# Uno.net
KiCad netlist of a schematic drawn in EAGLE
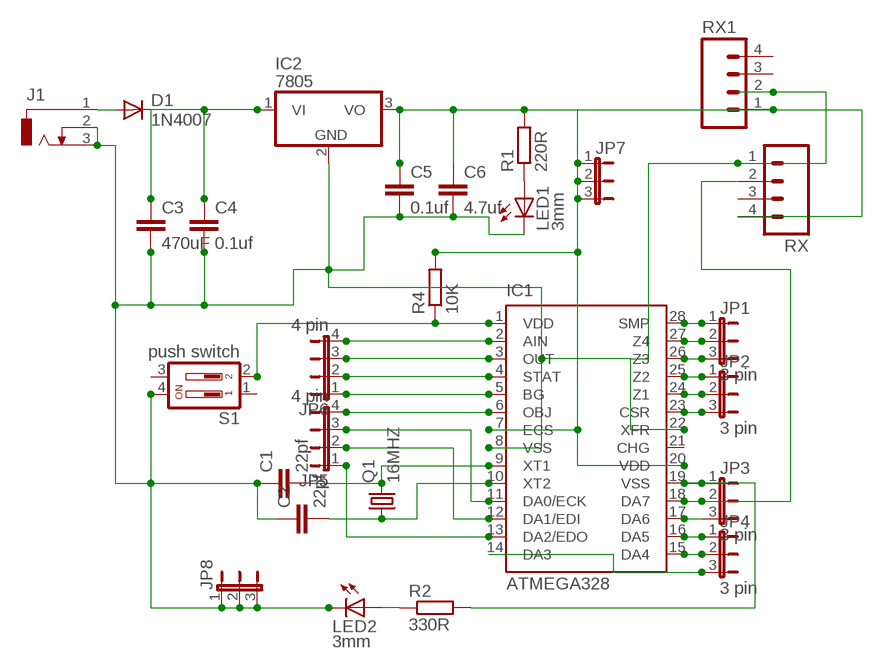
[diagram p0: schematic, sheet 1]

(export (version "E")
  (design (tool "Eeschema 10.0.6"))
  (components
    (comp (ref "C1")
      (value "22pf")
      (footprint "eagle-import:C2.5-2")
      (libsource (lib "eagle-import") (part "C2.5/2"))
    )
    (comp (ref "C2")
      (value "22pf")
      (footprint "eagle-import:C2.5-2")
      (libsource (lib "eagle-import") (part "C2.5/2"))
    )
    (comp (ref "C3")
      (value "470uF")
      (footprint "eagle-import:C2.5-2")
      (libsource (lib "eagle-import") (part "C2.5/2"))
    )
    (comp (ref "C4")
      (value "0.1uf")
      (footprint "eagle-import:C2.5-2")
      (libsource (lib "eagle-import") (part "C2.5/2"))
    )
    (comp (ref "C5")
      (value "0.1uf")
      (footprint "eagle-import:C2.5-2")
      (libsource (lib "eagle-import") (part "C2.5/2"))
    )
    (comp (ref "C6")
      (value "4.7uf")
      (footprint "eagle-import:C2.5-2")
      (libsource (lib "eagle-import") (part "C2.5/2"))
    )
    (comp (ref "D1")
      (value "1N4007")
      (footprint "eagle-import:DO41-10")
      (libsource (lib "eagle-import") (part "1N4004"))
    )
    (comp (ref "IC1")
      (value "ATMEGA328")
      (footprint "eagle-import:DIL28-3")
      (libsource (lib "eagle-import") (part "QT9701BD"))
    )
    (comp (ref "IC2")
      (value "7805")
      (footprint "eagle-import:TO220V")
      (libsource (lib "eagle-import") (part "78TV6"))
    )
    (comp (ref "J1")
      (value "DCJ0303")
      (footprint "eagle-import:DCJ0303")
      (libsource (lib "eagle-import") (part "DCJ0303"))
    )
    (comp (ref "JP1")
      (value "3 pin")
      (footprint "eagle-import:JP2")
      (libsource (lib "eagle-import") (part "JP2E"))
    )
    (comp (ref "JP2")
      (value "3 pin")
      (footprint "eagle-import:JP2")
      (libsource (lib "eagle-import") (part "JP2E"))
    )
    (comp (ref "JP3")
      (value "3 pin")
      (footprint "eagle-import:JP2")
      (libsource (lib "eagle-import") (part "JP2E"))
    )
    (comp (ref "JP4")
      (value "3 pin")
      (footprint "eagle-import:JP2")
      (libsource (lib "eagle-import") (part "JP2E"))
    )
    (comp (ref "JP5")
      (value "4 pin")
      (footprint "eagle-import:JP4")
      (libsource (lib "eagle-import") (part "JP4E"))
    )
    (comp (ref "JP6")
      (value "4 pin")
      (footprint "eagle-import:JP4")
      (libsource (lib "eagle-import") (part "JP4E"))
    )
    (comp (ref "JP7")
      (value "JP2E")
      (footprint "eagle-import:JP2")
      (libsource (lib "eagle-import") (part "JP2E"))
    )
    (comp (ref "JP8")
      (value "JP2E")
      (footprint "eagle-import:JP2")
      (libsource (lib "eagle-import") (part "JP2E"))
    )
    (comp (ref "LED1")
      (value "3mm")
      (footprint "eagle-import:LED3MM")
      (libsource (lib "eagle-import") (part "LED3MM"))
    )
    (comp (ref "LED2")
      (value "3mm")
      (footprint "eagle-import:LED3MM")
      (libsource (lib "eagle-import") (part "LED3MM"))
    )
    (comp (ref "Q1")
      (value "16MHZ")
      (footprint "eagle-import:HC49_S")
      (libsource (lib "eagle-import") (part "CRYSTALHC49S"))
    )
    (comp (ref "R1")
      (value "220R")
      (footprint "eagle-import:0207_10")
      (libsource (lib "eagle-import") (part "R-EU_0207/10"))
    )
    (comp (ref "R2")
      (value "330R")
      (footprint "eagle-import:0207_10")
      (libsource (lib "eagle-import") (part "R-EU_0207/10"))
    )
    (comp (ref "R4")
      (value "10K")
      (footprint "eagle-import:0207_10")
      (libsource (lib "eagle-import") (part "R-EU_0207/10"))
    )
    (comp (ref "RX")
      (value "M04")
      (footprint "eagle-import:04P")
      (libsource (lib "eagle-import") (part "M04"))
    )
    (comp (ref "RX1")
      (value "M04")
      (footprint "eagle-import:04P")
      (fields (field (name "OC_FARNELL") "unknown") (field (name "OC_NEWARK") "unknown"))
      (libsource (lib "eagle-import") (part "M04"))
    )
    (comp (ref "S1")
      (value "push switch")
      (footprint "eagle-import:DP-02")
      (fields (field (name "MPN") "MCDP02"))
      (libsource (lib "eagle-import") (part "DP02"))
    )
  )
  (nets
    (net (code "1") (name "Net-(D1-PadA)") (class "Default")
      (node (ref "D1") (pin "A") (pinfunction "A_A") (pintype "passive"))
      (node (ref "J1") (pin "1") (pinfunction "1_1") (pintype "passive"))
    )
    (net (code "2") (name "Net-(IC1-AIN)") (class "Default")
      (node (ref "IC1") (pin "2") (pinfunction "AIN_2") (pintype "input"))
      (node (ref "JP6") (pin "4") (pinfunction "4_4") (pintype "passive"))
    )
    (net (code "3") (name "Net-(IC1-BG)") (class "Default")
      (node (ref "IC1") (pin "5") (pinfunction "BG_5") (pintype "input"))
      (node (ref "JP6") (pin "1") (pinfunction "1_1") (pintype "passive"))
    )
    (net (code "4") (name "Net-(IC1-CSR)") (class "Default")
      (node (ref "IC1") (pin "23") (pinfunction "CSR_23") (pintype "output"))
      (node (ref "JP2") (pin "3") (pinfunction "3_3") (pintype "passive"))
    )
    (net (code "5") (name "Net-(IC1-DA0{slash}ECK)") (class "Default")
      (node (ref "IC1") (pin "11") (pinfunction "DA0/ECK_11") (pintype "output"))
      (node (ref "JP5") (pin "3") (pinfunction "3_3") (pintype "passive"))
    )
    (net (code "6") (name "Net-(IC1-DA1{slash}EDI)") (class "Default")
      (node (ref "IC1") (pin "12") (pinfunction "DA1/EDI_12") (pintype "output"))
      (node (ref "JP5") (pin "2") (pinfunction "2_2") (pintype "passive"))
    )
    (net (code "7") (name "Net-(IC1-DA2{slash}EDO)") (class "Default")
      (node (ref "IC1") (pin "13") (pinfunction "DA2/EDO_13") (pintype "output"))
      (node (ref "JP5") (pin "1") (pinfunction "1_1") (pintype "passive"))
    )
    (net (code "8") (name "Net-(IC1-DA3)") (class "Default")
      (node (ref "IC1") (pin "14") (pinfunction "DA3_14") (pintype "output"))
      (node (ref "JP4") (pin "3") (pinfunction "3_3") (pintype "passive"))
    )
    (net (code "9") (name "Net-(IC1-DA4)") (class "Default")
      (node (ref "IC1") (pin "15") (pinfunction "DA4_15") (pintype "output"))
      (node (ref "JP4") (pin "2") (pinfunction "2_2") (pintype "passive"))
    )
    (net (code "10") (name "Net-(IC1-DA5)") (class "Default")
      (node (ref "IC1") (pin "16") (pinfunction "DA5_16") (pintype "output"))
      (node (ref "JP4") (pin "1") (pinfunction "1_1") (pintype "passive"))
    )
    (net (code "11") (name "Net-(IC1-DA6)") (class "Default")
      (node (ref "IC1") (pin "17") (pinfunction "DA6_17") (pintype "output"))
      (node (ref "JP3") (pin "3") (pinfunction "3_3") (pintype "passive"))
    )
    (net (code "12") (name "Net-(IC1-DA7)") (class "Default")
      (node (ref "IC1") (pin "18") (pinfunction "DA7_18") (pintype "output"))
      (node (ref "JP3") (pin "2") (pinfunction "2_2") (pintype "passive"))
      (node (ref "RX") (pin "2") (pinfunction "2_2") (pintype "passive"))
    )
    (net (code "13") (name "Net-(IC1-ECS)") (class "Default")
      (node (ref "C5") (pin "1") (pinfunction "1_1") (pintype "passive"))
      (node (ref "C6") (pin "1") (pinfunction "1_1") (pintype "passive"))
      (node (ref "IC1") (pin "20") (pinfunction "VDD_20") (pintype "input"))
      (node (ref "IC1") (pin "7") (pinfunction "ECS_7") (pintype "output"))
      (node (ref "IC2") (pin "3") (pinfunction "VO_3") (pintype "passive"))
      (node (ref "JP7") (pin "1") (pinfunction "1_1") (pintype "passive"))
      (node (ref "JP7") (pin "2") (pinfunction "2_2") (pintype "passive"))
      (node (ref "JP7") (pin "3") (pinfunction "3_3") (pintype "passive"))
      (node (ref "R1") (pin "2") (pinfunction "2_2") (pintype "passive"))
      (node (ref "R4") (pin "2") (pinfunction "2_2") (pintype "passive"))
      (node (ref "RX") (pin "4") (pinfunction "4_4") (pintype "passive"))
      (node (ref "RX1") (pin "1") (pinfunction "1_1") (pintype "passive"))
    )
    (net (code "14") (name "Net-(IC1-OBJ)") (class "Default")
      (node (ref "IC1") (pin "6") (pinfunction "OBJ_6") (pintype "input"))
      (node (ref "JP5") (pin "4") (pinfunction "4_4") (pintype "passive"))
    )
    (net (code "15") (name "Net-(IC1-OUT)") (class "Default")
      (node (ref "IC1") (pin "3") (pinfunction "OUT_3") (pintype "output"))
      (node (ref "JP6") (pin "3") (pinfunction "3_3") (pintype "passive"))
    )
    (net (code "16") (name "Net-(IC1-SMP)") (class "Default")
      (node (ref "IC1") (pin "28") (pinfunction "SMP_28") (pintype "output"))
      (node (ref "JP1") (pin "1") (pinfunction "1_1") (pintype "passive"))
    )
    (net (code "17") (name "Net-(IC1-STAT)") (class "Default")
      (node (ref "IC1") (pin "4") (pinfunction "STAT_4") (pintype "output"))
      (node (ref "JP6") (pin "2") (pinfunction "2_2") (pintype "passive"))
    )
    (net (code "18") (name "Net-(IC1-VDD-Pad1)") (class "Default")
      (node (ref "IC1") (pin "1") (pinfunction "VDD_1") (pintype "input"))
      (node (ref "R4") (pin "1") (pinfunction "1_1") (pintype "passive"))
      (node (ref "S1") (pin "2") (pinfunction "2_2") (pintype "passive"))
    )
    (net (code "19") (name "Net-(IC1-VSS-Pad19)") (class "Default")
      (node (ref "IC1") (pin "19") (pinfunction "VSS_19") (pintype "input"))
      (node (ref "JP3") (pin "1") (pinfunction "1_1") (pintype "passive"))
      (node (ref "R2") (pin "2") (pinfunction "2_2") (pintype "passive"))
    )
    (net (code "20") (name "Net-(IC1-XFR)") (class "Default")
      (node (ref "C1") (pin "1") (pinfunction "1_1") (pintype "passive"))
      (node (ref "C2") (pin "1") (pinfunction "1_1") (pintype "passive"))
      (node (ref "C3") (pin "2") (pinfunction "2_2") (pintype "passive"))
      (node (ref "C4") (pin "2") (pinfunction "2_2") (pintype "passive"))
      (node (ref "C5") (pin "2") (pinfunction "2_2") (pintype "passive"))
      (node (ref "C6") (pin "2") (pinfunction "2_2") (pintype "passive"))
      (node (ref "IC1") (pin "22") (pinfunction "XFR_22") (pintype "output"))
      (node (ref "IC1") (pin "8") (pinfunction "VSS_8") (pintype "input"))
      (node (ref "IC2") (pin "2") (pinfunction "GND_2") (pintype "passive"))
      (node (ref "J1") (pin "2") (pinfunction "2_2") (pintype "passive"))
      (node (ref "J1") (pin "3") (pinfunction "3_3") (pintype "passive"))
      (node (ref "JP8") (pin "1") (pinfunction "1_1") (pintype "passive"))
      (node (ref "JP8") (pin "2") (pinfunction "2_2") (pintype "passive"))
      (node (ref "JP8") (pin "3") (pinfunction "3_3") (pintype "passive"))
      (node (ref "LED1") (pin "K") (pinfunction "C_K") (pintype "passive"))
      (node (ref "LED2") (pin "K") (pinfunction "C_K") (pintype "passive"))
      (node (ref "RX") (pin "1") (pinfunction "1_1") (pintype "passive"))
      (node (ref "RX1") (pin "2") (pinfunction "2_2") (pintype "passive"))
      (node (ref "S1") (pin "4") (pinfunction "4_4") (pintype "passive"))
    )
    (net (code "21") (name "Net-(IC1-XT1)") (class "Default")
      (node (ref "C1") (pin "2") (pinfunction "2_2") (pintype "passive"))
      (node (ref "IC1") (pin "9") (pinfunction "XT1_9") (pintype "input"))
      (node (ref "Q1") (pin "2") (pinfunction "2_2") (pintype "passive"))
    )
    (net (code "22") (name "Net-(IC1-XT2)") (class "Default")
      (node (ref "C2") (pin "2") (pinfunction "2_2") (pintype "passive"))
      (node (ref "IC1") (pin "10") (pinfunction "XT2_10") (pintype "output"))
      (node (ref "Q1") (pin "1") (pinfunction "1_1") (pintype "passive"))
    )
    (net (code "23") (name "Net-(IC1-Z1)") (class "Default")
      (node (ref "IC1") (pin "24") (pinfunction "Z1_24") (pintype "output"))
      (node (ref "JP2") (pin "2") (pinfunction "2_2") (pintype "passive"))
    )
    (net (code "24") (name "Net-(IC1-Z2)") (class "Default")
      (node (ref "IC1") (pin "25") (pinfunction "Z2_25") (pintype "output"))
      (node (ref "JP2") (pin "1") (pinfunction "1_1") (pintype "passive"))
    )
    (net (code "25") (name "Net-(IC1-Z3)") (class "Default")
      (node (ref "IC1") (pin "26") (pinfunction "Z3_26") (pintype "output"))
      (node (ref "JP1") (pin "3") (pinfunction "3_3") (pintype "passive"))
    )
    (net (code "26") (name "Net-(IC1-Z4)") (class "Default")
      (node (ref "IC1") (pin "27") (pinfunction "Z4_27") (pintype "output"))
      (node (ref "JP1") (pin "2") (pinfunction "2_2") (pintype "passive"))
    )
    (net (code "27") (name "Net-(IC2-VI)") (class "Default")
      (node (ref "C3") (pin "1") (pinfunction "1_1") (pintype "passive"))
      (node (ref "C4") (pin "1") (pinfunction "1_1") (pintype "passive"))
      (node (ref "D1") (pin "C") (pinfunction "C_C") (pintype "passive"))
      (node (ref "IC2") (pin "1") (pinfunction "VI_1") (pintype "input"))
    )
    (net (code "28") (name "Net-(LED1-PadA)") (class "Default")
      (node (ref "LED1") (pin "A") (pinfunction "A_A") (pintype "passive"))
      (node (ref "R1") (pin "1") (pinfunction "1_1") (pintype "passive"))
    )
    (net (code "29") (name "Net-(LED2-PadA)") (class "Default")
      (node (ref "LED2") (pin "A") (pinfunction "A_A") (pintype "passive"))
      (node (ref "R2") (pin "1") (pinfunction "1_1") (pintype "passive"))
    )
    (net (code "30") (name "unconnected-(IC1-CHG-Pad21)") (class "Default")
      (node (ref "IC1") (pin "21") (pinfunction "CHG_21") (pintype "output"))
    )
    (net (code "31") (name "unconnected-(RX-Pad3)") (class "Default")
      (node (ref "RX") (pin "3") (pinfunction "3_3") (pintype "passive"))
    )
    (net (code "32") (name "unconnected-(RX1-Pad3)") (class "Default")
      (node (ref "RX1") (pin "3") (pinfunction "3_3") (pintype "passive"))
    )
    (net (code "33") (name "unconnected-(RX1-Pad4)") (class "Default")
      (node (ref "RX1") (pin "4") (pinfunction "4_4") (pintype "passive"))
    )
    (net (code "34") (name "unconnected-(S1-Pad1)") (class "Default")
      (node (ref "S1") (pin "1") (pinfunction "1_1") (pintype "passive"))
    )
    (net (code "35") (name "unconnected-(S1-Pad3)") (class "Default")
      (node (ref "S1") (pin "3") (pinfunction "3_3") (pintype "passive"))
    )
  )
)
